# bluc_r3.net
KiCad netlist of a schematic drawn in EAGLE
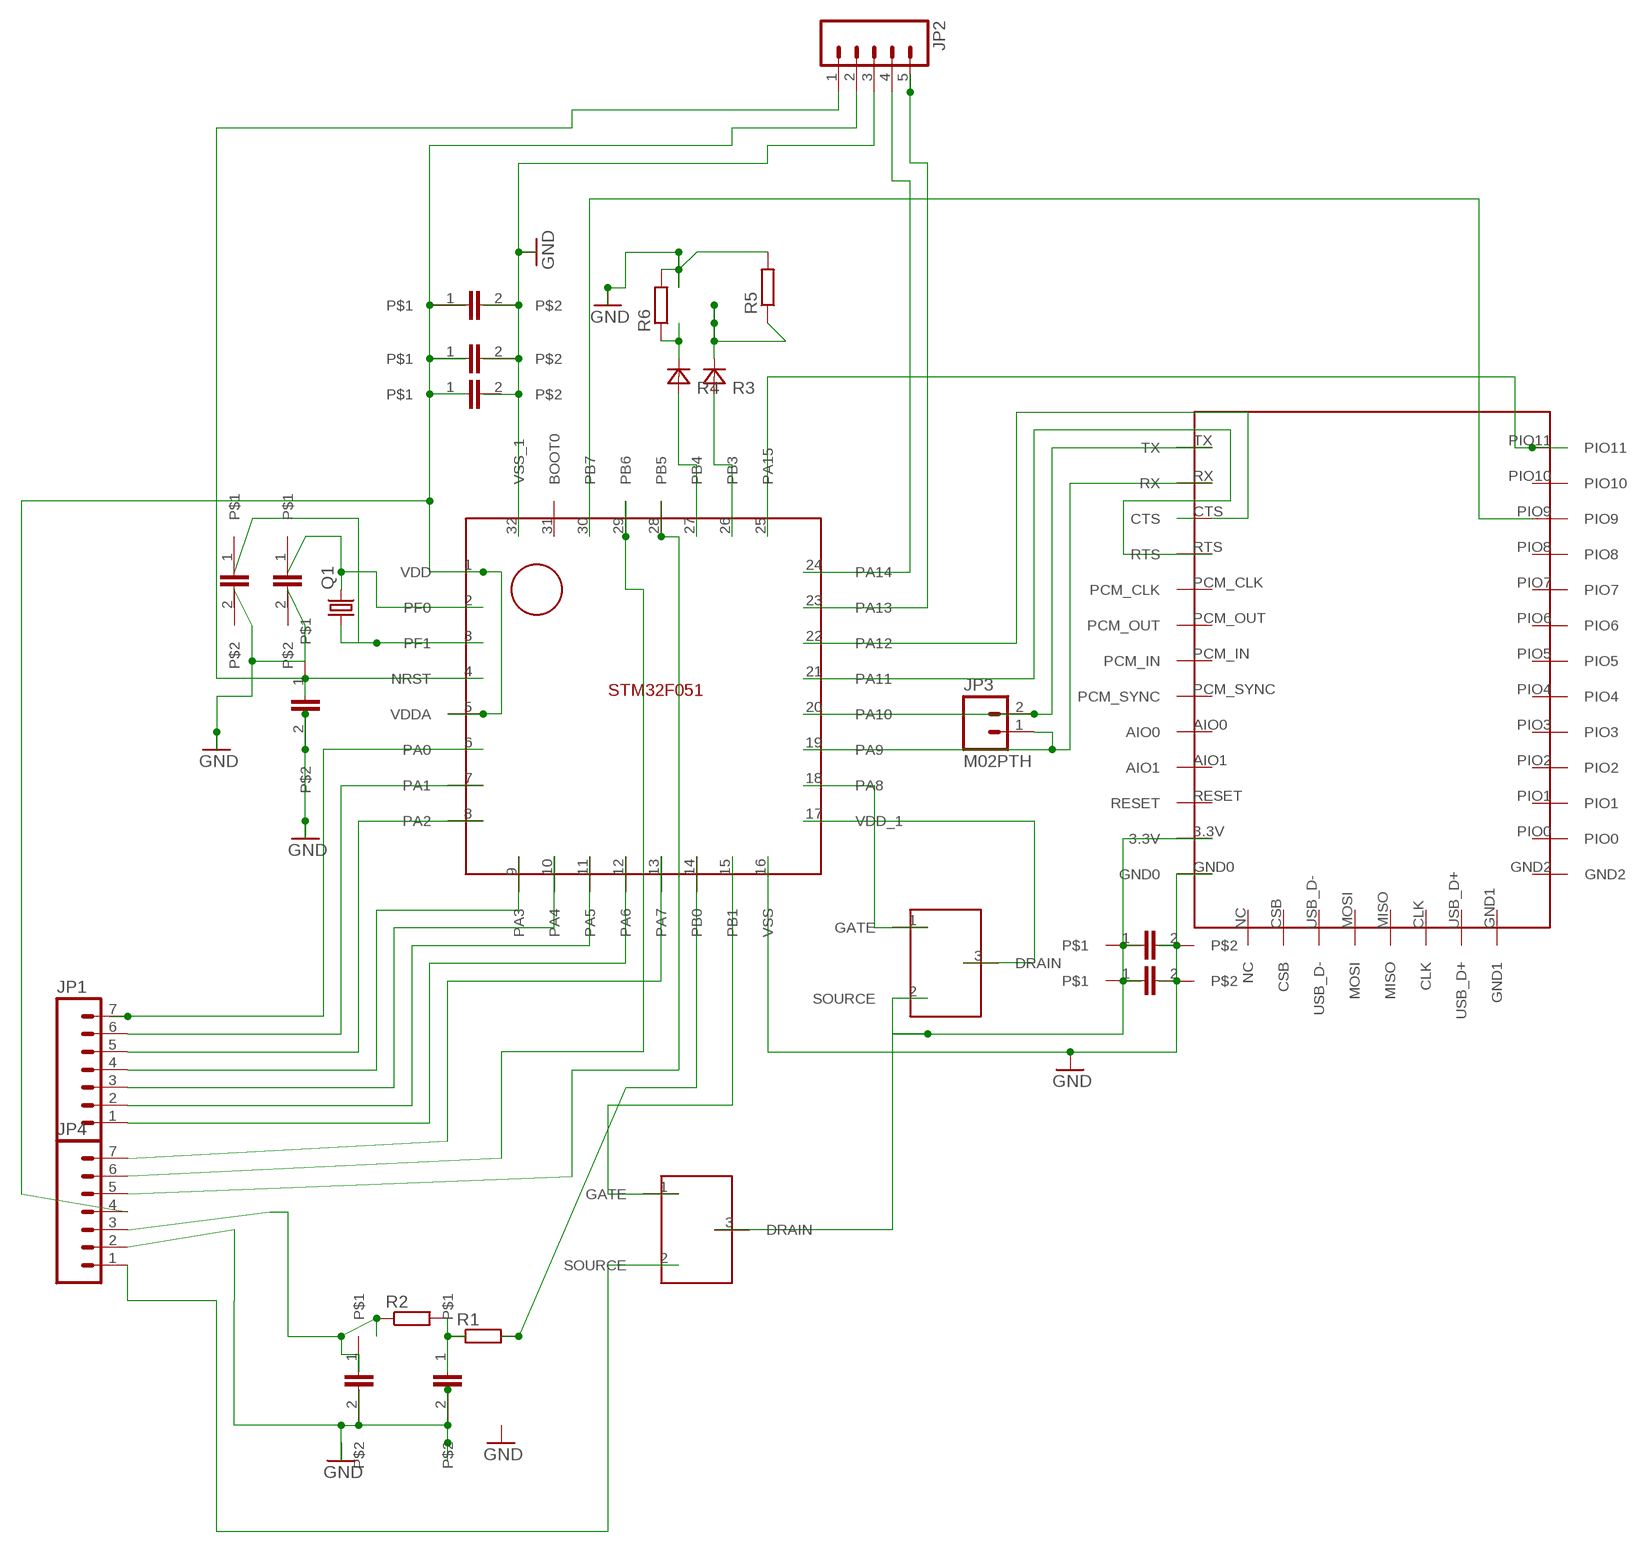
[diagram p0: schematic, sheet 1]

(export (version "E")
  (design (tool "Eeschema 10.0.6"))
  (components
    (comp (ref "JP1")
      (value "M07")
      (footprint "eagle-import:1X07")
      (libsource (lib "eagle-import") (part "M07"))
    )
    (comp (ref "JP2")
      (value "M05PTH")
      (footprint "eagle-import:1X05")
      (libsource (lib "eagle-import") (part "M05PTH"))
    )
    (comp (ref "JP3")
      (value "M02PTH")
      (footprint "eagle-import:1X02")
      (libsource (lib "eagle-import") (part "M02PTH"))
    )
    (comp (ref "JP4")
      (value "M07")
      (footprint "eagle-import:1X07")
      (libsource (lib "eagle-import") (part "M07"))
    )
    (comp (ref "Q1")
      (value "CRYSTAL")
      (footprint "eagle-import:32768_CRYSTAL_PACKAGE")
      (libsource (lib "eagle-import") (part "CRYSTAL"))
    )
    (comp (ref "R1")
      (value "R-EU_R0603")
      (footprint "eagle-import:R0603")
      (libsource (lib "eagle-import") (part "R-EU_R0603"))
    )
    (comp (ref "R2")
      (value "R-EU_R0603")
      (footprint "eagle-import:R0603")
      (libsource (lib "eagle-import") (part "R-EU_R0603"))
    )
    (comp (ref "R3")
      (value "DIODE")
      (footprint "eagle-import:C0805K")
      (libsource (lib "eagle-import") (part "DIODE"))
    )
    (comp (ref "R4")
      (value "DIODE")
      (footprint "eagle-import:C0805K")
      (libsource (lib "eagle-import") (part "DIODE"))
    )
    (comp (ref "R5")
      (value "R-EU_R0603")
      (footprint "eagle-import:R0603")
      (libsource (lib "eagle-import") (part "R-EU_R0603"))
    )
    (comp (ref "R6")
      (value "R-EU_R0603")
      (footprint "eagle-import:R0603")
      (libsource (lib "eagle-import") (part "R-EU_R0603"))
    )
    (comp (ref "U$1")
      (value "STM32F051")
      (footprint "eagle-import:LQFP32-7X7")
      (libsource (lib "eagle-import") (part "STM32F051"))
    )
    (comp (ref "U$2")
      (value "HC-05")
      (footprint "eagle-import:HC-05")
      (libsource (lib "eagle-import") (part "HC-05"))
    )
    (comp (ref "U$3")
      (value "2N7002K")
      (footprint "eagle-import:SOT23")
      (libsource (lib "eagle-import") (part "2N7002K"))
    )
    (comp (ref "U$4")
      (value "2N7002K")
      (footprint "eagle-import:SOT23")
      (libsource (lib "eagle-import") (part "2N7002K"))
    )
    (comp (ref "U$5")
      (value "C0.1UF")
      (footprint "eagle-import:C0805K")
      (libsource (lib "eagle-import") (part "C0.1UF"))
    )
    (comp (ref "U$6")
      (value "C0.1UF")
      (footprint "eagle-import:C0805K")
      (libsource (lib "eagle-import") (part "C0.1UF"))
    )
    (comp (ref "U$7")
      (value "C0.1UF")
      (footprint "eagle-import:C0805K")
      (libsource (lib "eagle-import") (part "C0.1UF"))
    )
    (comp (ref "U$8")
      (value "C0.1UF")
      (footprint "eagle-import:C0805K")
      (libsource (lib "eagle-import") (part "C0.1UF"))
    )
    (comp (ref "U$9")
      (value "C0.1UF")
      (footprint "eagle-import:C0805K")
      (libsource (lib "eagle-import") (part "C0.1UF"))
    )
    (comp (ref "U$10")
      (value "C0.1UF")
      (footprint "eagle-import:C0805K")
      (libsource (lib "eagle-import") (part "C0.1UF"))
    )
    (comp (ref "U$11")
      (value "C1UF")
      (footprint "eagle-import:C0805K")
      (libsource (lib "eagle-import") (part "C1UF"))
    )
    (comp (ref "U$12")
      (value "C1UF")
      (footprint "eagle-import:C0805K")
      (libsource (lib "eagle-import") (part "C1UF"))
    )
    (comp (ref "U$13")
      (value "C0.1UF")
      (footprint "eagle-import:C0805K")
      (libsource (lib "eagle-import") (part "C0.1UF"))
    )
    (comp (ref "U$14")
      (value "C0.1UF")
      (footprint "eagle-import:C0805K")
      (libsource (lib "eagle-import") (part "C0.1UF"))
    )
  )
  (nets
    (net (code "1") (name "GND") (class "Default")
      (node (ref "JP2") (pin "3") (pinfunction "3_3") (pintype "passive"))
      (node (ref "JP4") (pin "2") (pinfunction "2_2") (pintype "passive"))
      (node (ref "R5") (pin "2") (pinfunction "2_2") (pintype "passive"))
      (node (ref "R6") (pin "2") (pinfunction "2_2") (pintype "passive"))
      (node (ref "U$1") (pin "16") (pinfunction "VSS_16") (pintype "bidirectional"))
      (node (ref "U$1") (pin "32") (pinfunction "VSS_1_32") (pintype "bidirectional"))
      (node (ref "U$10") (pin "2") (pinfunction "P$2_2") (pintype "bidirectional"))
      (node (ref "U$11") (pin "2") (pinfunction "P$2_2") (pintype "bidirectional"))
      (node (ref "U$12") (pin "2") (pinfunction "P$2_2") (pintype "bidirectional"))
      (node (ref "U$13") (pin "2") (pinfunction "P$2_2") (pintype "bidirectional"))
      (node (ref "U$14") (pin "2") (pinfunction "P$2_2") (pintype "bidirectional"))
      (node (ref "U$2") (pin "GND0") (pinfunction "GND0_GND0") (pintype "bidirectional"))
      (node (ref "U$5") (pin "2") (pinfunction "P$2_2") (pintype "bidirectional"))
      (node (ref "U$6") (pin "2") (pinfunction "P$2_2") (pintype "bidirectional"))
      (node (ref "U$7") (pin "2") (pinfunction "P$2_2") (pintype "bidirectional"))
      (node (ref "U$8") (pin "2") (pinfunction "P$2_2") (pintype "bidirectional"))
      (node (ref "U$9") (pin "2") (pinfunction "P$2_2") (pintype "bidirectional"))
    )
    (net (code "2") (name "Net-(Q1-2)") (class "Default")
      (node (ref "Q1") (pin "4") (pinfunction "2_4") (pintype "passive"))
      (node (ref "U$1") (pin "2") (pinfunction "PF0_2") (pintype "bidirectional"))
      (node (ref "U$13") (pin "1") (pinfunction "P$1_1") (pintype "bidirectional"))
    )
    (net (code "3") (name "Net-(R3-A)") (class "Default")
      (node (ref "R3") (pin "1") (pinfunction "A_1") (pintype "input"))
      (node (ref "R5") (pin "1") (pinfunction "1_1") (pintype "passive"))
    )
    (net (code "4") (name "Net-(R3-C)") (class "Default")
      (node (ref "R3") (pin "2") (pinfunction "C_2") (pintype "input"))
      (node (ref "U$1") (pin "26") (pinfunction "PB3_26") (pintype "bidirectional"))
    )
    (net (code "5") (name "Net-(R4-A)") (class "Default")
      (node (ref "R4") (pin "1") (pinfunction "A_1") (pintype "input"))
      (node (ref "R6") (pin "1") (pinfunction "1_1") (pintype "passive"))
    )
    (net (code "6") (name "Net-(R4-C)") (class "Default")
      (node (ref "R4") (pin "2") (pinfunction "C_2") (pintype "input"))
      (node (ref "U$1") (pin "27") (pinfunction "PB4_27") (pintype "bidirectional"))
    )
    (net (code "7") (name "Net-(U$1-NRST)") (class "Default")
      (node (ref "JP2") (pin "1") (pinfunction "1_1") (pintype "passive"))
      (node (ref "U$1") (pin "4") (pinfunction "NRST_4") (pintype "bidirectional"))
      (node (ref "U$10") (pin "1") (pinfunction "P$1_1") (pintype "bidirectional"))
    )
    (net (code "8") (name "Net-(U$1-PA0)") (class "Default")
      (node (ref "JP1") (pin "7") (pinfunction "7_7") (pintype "passive"))
      (node (ref "U$1") (pin "6") (pinfunction "PA0_6") (pintype "bidirectional"))
    )
    (net (code "9") (name "Net-(U$1-PA1)") (class "Default")
      (node (ref "JP1") (pin "6") (pinfunction "6_6") (pintype "passive"))
      (node (ref "U$1") (pin "7") (pinfunction "PA1_7") (pintype "bidirectional"))
    )
    (net (code "10") (name "Net-(U$1-PA2)") (class "Default")
      (node (ref "JP1") (pin "5") (pinfunction "5_5") (pintype "passive"))
      (node (ref "U$1") (pin "8") (pinfunction "PA2_8") (pintype "bidirectional"))
    )
    (net (code "11") (name "Net-(U$1-PA3)") (class "Default")
      (node (ref "JP1") (pin "4") (pinfunction "4_4") (pintype "passive"))
      (node (ref "U$1") (pin "9") (pinfunction "PA3_9") (pintype "bidirectional"))
    )
    (net (code "12") (name "Net-(U$1-PA4)") (class "Default")
      (node (ref "JP1") (pin "3") (pinfunction "3_3") (pintype "passive"))
      (node (ref "U$1") (pin "10") (pinfunction "PA4_10") (pintype "bidirectional"))
    )
    (net (code "13") (name "Net-(U$1-PA5)") (class "Default")
      (node (ref "JP1") (pin "2") (pinfunction "2_2") (pintype "passive"))
      (node (ref "U$1") (pin "11") (pinfunction "PA5_11") (pintype "bidirectional"))
    )
    (net (code "14") (name "Net-(U$1-PA6)") (class "Default")
      (node (ref "JP1") (pin "1") (pinfunction "1_1") (pintype "passive"))
      (node (ref "U$1") (pin "12") (pinfunction "PA6_12") (pintype "bidirectional"))
    )
    (net (code "15") (name "Net-(U$1-PA7)") (class "Default")
      (node (ref "JP4") (pin "7") (pinfunction "7_7") (pintype "passive"))
      (node (ref "U$1") (pin "13") (pinfunction "PA7_13") (pintype "bidirectional"))
    )
    (net (code "16") (name "Net-(U$1-PA8)") (class "Default")
      (node (ref "U$1") (pin "18") (pinfunction "PA8_18") (pintype "bidirectional"))
      (node (ref "U$3") (pin "1") (pinfunction "GATE_1") (pintype "bidirectional"))
    )
    (net (code "17") (name "Net-(U$1-PA9)") (class "Default")
      (node (ref "JP3") (pin "1") (pinfunction "1_1") (pintype "passive"))
      (node (ref "U$1") (pin "19") (pinfunction "PA9_19") (pintype "bidirectional"))
      (node (ref "U$2") (pin "RX") (pinfunction "RX_RX") (pintype "bidirectional"))
    )
    (net (code "18") (name "Net-(U$1-PA10)") (class "Default")
      (node (ref "JP3") (pin "2") (pinfunction "2_2") (pintype "passive"))
      (node (ref "U$1") (pin "20") (pinfunction "PA10_20") (pintype "bidirectional"))
      (node (ref "U$2") (pin "TX") (pinfunction "TX_TX") (pintype "bidirectional"))
    )
    (net (code "19") (name "Net-(U$1-PA11)") (class "Default")
      (node (ref "U$1") (pin "21") (pinfunction "PA11_21") (pintype "bidirectional"))
      (node (ref "U$2") (pin "RTS") (pinfunction "RTS_RTS") (pintype "bidirectional"))
    )
    (net (code "20") (name "Net-(U$1-PA12)") (class "Default")
      (node (ref "U$1") (pin "22") (pinfunction "PA12_22") (pintype "bidirectional"))
      (node (ref "U$2") (pin "CTS") (pinfunction "CTS_CTS") (pintype "bidirectional"))
    )
    (net (code "21") (name "Net-(U$1-PA13)") (class "Default")
      (node (ref "JP2") (pin "5") (pinfunction "5_5") (pintype "passive"))
      (node (ref "U$1") (pin "23") (pinfunction "PA13_23") (pintype "bidirectional"))
    )
    (net (code "22") (name "Net-(U$1-PA14)") (class "Default")
      (node (ref "JP2") (pin "4") (pinfunction "4_4") (pintype "passive"))
      (node (ref "U$1") (pin "24") (pinfunction "PA14_24") (pintype "bidirectional"))
    )
    (net (code "23") (name "Net-(U$1-PA15)") (class "Default")
      (node (ref "U$1") (pin "25") (pinfunction "PA15_25") (pintype "bidirectional"))
      (node (ref "U$2") (pin "PIO11") (pinfunction "PIO11_PIO11") (pintype "bidirectional"))
    )
    (net (code "24") (name "Net-(U$1-PB0)") (class "Default")
      (node (ref "R1") (pin "2") (pinfunction "2_2") (pintype "passive"))
      (node (ref "U$1") (pin "14") (pinfunction "PB0_14") (pintype "bidirectional"))
    )
    (net (code "25") (name "Net-(U$1-PB1)") (class "Default")
      (node (ref "U$1") (pin "15") (pinfunction "PB1_15") (pintype "bidirectional"))
      (node (ref "U$4") (pin "1") (pinfunction "GATE_1") (pintype "bidirectional"))
    )
    (net (code "26") (name "Net-(U$1-PB5)") (class "Default")
      (node (ref "JP4") (pin "5") (pinfunction "5_5") (pintype "passive"))
      (node (ref "U$1") (pin "28") (pinfunction "PB5_28") (pintype "bidirectional"))
    )
    (net (code "27") (name "Net-(U$1-PB6)") (class "Default")
      (node (ref "JP4") (pin "6") (pinfunction "6_6") (pintype "passive"))
      (node (ref "U$1") (pin "29") (pinfunction "PB6_29") (pintype "bidirectional"))
    )
    (net (code "28") (name "Net-(U$1-PB7)") (class "Default")
      (node (ref "U$1") (pin "30") (pinfunction "PB7_30") (pintype "bidirectional"))
      (node (ref "U$2") (pin "PIO9") (pinfunction "PIO9_PIO9") (pintype "bidirectional"))
    )
    (net (code "29") (name "Net-(U$1-PF1)") (class "Default")
      (node (ref "Q1") (pin "1") (pinfunction "1_1") (pintype "passive"))
      (node (ref "U$1") (pin "3") (pinfunction "PF1_3") (pintype "bidirectional"))
      (node (ref "U$14") (pin "1") (pinfunction "P$1_1") (pintype "bidirectional"))
    )
    (net (code "30") (name "Net-(U$1-VDD)") (class "Default")
      (node (ref "JP2") (pin "2") (pinfunction "2_2") (pintype "passive"))
      (node (ref "JP4") (pin "4") (pinfunction "4_4") (pintype "passive"))
      (node (ref "U$1") (pin "1") (pinfunction "VDD_1") (pintype "bidirectional"))
      (node (ref "U$1") (pin "5") (pinfunction "VDDA_5") (pintype "bidirectional"))
      (node (ref "U$7") (pin "1") (pinfunction "P$1_1") (pintype "bidirectional"))
      (node (ref "U$8") (pin "1") (pinfunction "P$1_1") (pintype "bidirectional"))
      (node (ref "U$9") (pin "1") (pinfunction "P$1_1") (pintype "bidirectional"))
    )
    (net (code "31") (name "Net-(U$1-VDD_1)") (class "Default")
      (node (ref "U$1") (pin "17") (pinfunction "VDD_1_17") (pintype "bidirectional"))
      (node (ref "U$3") (pin "3") (pinfunction "DRAIN_3") (pintype "bidirectional"))
    )
    (net (code "32") (name "Net-(U$3-SOURCE)") (class "Default")
      (node (ref "U$2") (pin "3.3V") (pinfunction "3.3V_3.3V") (pintype "bidirectional"))
      (node (ref "U$3") (pin "2") (pinfunction "SOURCE_2") (pintype "bidirectional"))
      (node (ref "U$4") (pin "3") (pinfunction "DRAIN_3") (pintype "bidirectional"))
      (node (ref "U$5") (pin "1") (pinfunction "P$1_1") (pintype "bidirectional"))
      (node (ref "U$6") (pin "1") (pinfunction "P$1_1") (pintype "bidirectional"))
    )
    (net (code "33") (name "Net-(U$4-SOURCE)") (class "Default")
      (node (ref "JP4") (pin "1") (pinfunction "1_1") (pintype "passive"))
      (node (ref "U$4") (pin "2") (pinfunction "SOURCE_2") (pintype "bidirectional"))
    )
    (net (code "34") (name "Net-(U$11-P$1)") (class "Default")
      (node (ref "R1") (pin "1") (pinfunction "1_1") (pintype "passive"))
      (node (ref "R2") (pin "2") (pinfunction "2_2") (pintype "passive"))
      (node (ref "U$11") (pin "1") (pinfunction "P$1_1") (pintype "bidirectional"))
    )
    (net (code "35") (name "Net-(U$12-P$1)") (class "Default")
      (node (ref "JP4") (pin "3") (pinfunction "3_3") (pintype "passive"))
      (node (ref "R2") (pin "1") (pinfunction "1_1") (pintype "passive"))
      (node (ref "U$12") (pin "1") (pinfunction "P$1_1") (pintype "bidirectional"))
    )
    (net (code "36") (name "unconnected-(U$1-BOOT0-Pad31)") (class "Default")
      (node (ref "U$1") (pin "31") (pinfunction "BOOT0_31") (pintype "bidirectional"))
    )
    (net (code "37") (name "unconnected-(U$2-PadAIO0)") (class "Default")
      (node (ref "U$2") (pin "AIO0") (pinfunction "AIO0_AIO0") (pintype "bidirectional"))
    )
    (net (code "38") (name "unconnected-(U$2-PadAIO1)") (class "Default")
      (node (ref "U$2") (pin "AIO1") (pinfunction "AIO1_AIO1") (pintype "bidirectional"))
    )
    (net (code "39") (name "unconnected-(U$2-PadCLK)") (class "Default")
      (node (ref "U$2") (pin "CLK") (pinfunction "CLK_CLK") (pintype "bidirectional"))
    )
    (net (code "40") (name "unconnected-(U$2-PadCSB)") (class "Default")
      (node (ref "U$2") (pin "CSB") (pinfunction "CSB_CSB") (pintype "bidirectional"))
    )
    (net (code "41") (name "unconnected-(U$2-PadGND1)") (class "Default")
      (node (ref "U$2") (pin "GND1") (pinfunction "GND1_GND1") (pintype "bidirectional"))
    )
    (net (code "42") (name "unconnected-(U$2-PadGND2)") (class "Default")
      (node (ref "U$2") (pin "GND2") (pinfunction "GND2_GND2") (pintype "bidirectional"))
    )
    (net (code "43") (name "unconnected-(U$2-PadMISO)") (class "Default")
      (node (ref "U$2") (pin "MISO") (pinfunction "MISO_MISO") (pintype "bidirectional"))
    )
    (net (code "44") (name "unconnected-(U$2-PadMOSI)") (class "Default")
      (node (ref "U$2") (pin "MOSI") (pinfunction "MOSI_MOSI") (pintype "bidirectional"))
    )
    (net (code "45") (name "unconnected-(U$2-PadNC)") (class "Default")
      (node (ref "U$2") (pin "NC") (pinfunction "NC_NC") (pintype "bidirectional"))
    )
    (net (code "46") (name "unconnected-(U$2-PadPCM_CLK)") (class "Default")
      (node (ref "U$2") (pin "PCM_CLK") (pinfunction "PCM_CLK_PCM_CLK") (pintype "bidirectional"))
    )
    (net (code "47") (name "unconnected-(U$2-PadPCM_IN)") (class "Default")
      (node (ref "U$2") (pin "PCM_IN") (pinfunction "PCM_IN_PCM_IN") (pintype "bidirectional"))
    )
    (net (code "48") (name "unconnected-(U$2-PadPCM_OUT)") (class "Default")
      (node (ref "U$2") (pin "PCM_OUT") (pinfunction "PCM_OUT_PCM_OUT") (pintype "bidirectional"))
    )
    (net (code "49") (name "unconnected-(U$2-PadPCM_SYNC)") (class "Default")
      (node (ref "U$2") (pin "PCM_SYNC") (pinfunction "PCM_SYNC_PCM_SYNC") (pintype "bidirectional"))
    )
    (net (code "50") (name "unconnected-(U$2-PadPIO0)") (class "Default")
      (node (ref "U$2") (pin "PIO0") (pinfunction "PIO0_PIO0") (pintype "bidirectional"))
    )
    (net (code "51") (name "unconnected-(U$2-PadPIO1)") (class "Default")
      (node (ref "U$2") (pin "PIO1") (pinfunction "PIO1_PIO1") (pintype "bidirectional"))
    )
    (net (code "52") (name "unconnected-(U$2-PadPIO2)") (class "Default")
      (node (ref "U$2") (pin "PIO2") (pinfunction "PIO2_PIO2") (pintype "bidirectional"))
    )
    (net (code "53") (name "unconnected-(U$2-PadPIO3)") (class "Default")
      (node (ref "U$2") (pin "PIO3") (pinfunction "PIO3_PIO3") (pintype "bidirectional"))
    )
    (net (code "54") (name "unconnected-(U$2-PadPIO4)") (class "Default")
      (node (ref "U$2") (pin "PIO4") (pinfunction "PIO4_PIO4") (pintype "bidirectional"))
    )
    (net (code "55") (name "unconnected-(U$2-PadPIO5)") (class "Default")
      (node (ref "U$2") (pin "PIO5") (pinfunction "PIO5_PIO5") (pintype "bidirectional"))
    )
    (net (code "56") (name "unconnected-(U$2-PadPIO6)") (class "Default")
      (node (ref "U$2") (pin "PIO6") (pinfunction "PIO6_PIO6") (pintype "bidirectional"))
    )
    (net (code "57") (name "unconnected-(U$2-PadPIO7)") (class "Default")
      (node (ref "U$2") (pin "PIO7") (pinfunction "PIO7_PIO7") (pintype "bidirectional"))
    )
    (net (code "58") (name "unconnected-(U$2-PadPIO8)") (class "Default")
      (node (ref "U$2") (pin "PIO8") (pinfunction "PIO8_PIO8") (pintype "bidirectional"))
    )
    (net (code "59") (name "unconnected-(U$2-PadPIO10)") (class "Default")
      (node (ref "U$2") (pin "PIO10") (pinfunction "PIO10_PIO10") (pintype "bidirectional"))
    )
    (net (code "60") (name "unconnected-(U$2-PadRESET)") (class "Default")
      (node (ref "U$2") (pin "RESET") (pinfunction "RESET_RESET") (pintype "bidirectional"))
    )
    (net (code "61") (name "unconnected-(U$2-PadUSB_D+)") (class "Default")
      (node (ref "U$2") (pin "USB_D+") (pinfunction "USB_D+_USB_D+") (pintype "bidirectional"))
    )
    (net (code "62") (name "unconnected-(U$2-PadUSB_D-)") (class "Default")
      (node (ref "U$2") (pin "USB_D-") (pinfunction "USB_D-_USB_D-") (pintype "bidirectional"))
    )
  )
)
